# Detect220V.net
KiCad netlist of a schematic drawn in Altium Designer
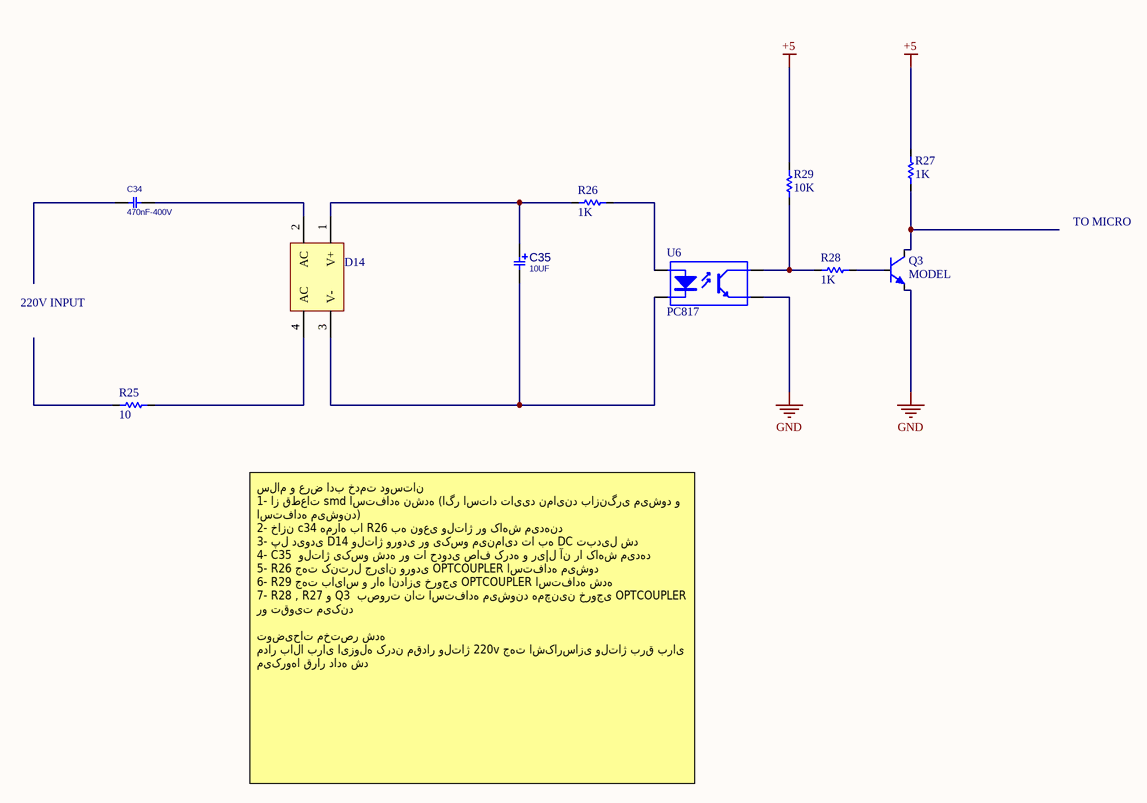
[diagram p0: Detect220V.SchDoc]

(export (version "E")
  (design (tool "Eeschema 10.0.6"))
  (components
    (comp (ref "C34")
      (value "470nF-400V")
      (footprint "C_PLY_6X2_5")
      (description "CAP, FILM,")
      (fields (field (name "MANF_P#") "MANF_PART#") (field (name "MANF") "MANF"))
      (libsource (lib "PASSIVE") (part "CAP_THD_FILM_POLYESTER"))
    )
    (comp (ref "C35")
      (value "10UF")
      (footprint "C_EL_4X7")
      (description "CAP, THD, ELEC,")
      (fields (field (name "MANF_P#") "MANF_PART#") (field (name "MANF") "MANF"))
      (libsource (lib "PASSIVE") (part "CAP_THD_EL"))
    )
    (comp (ref "D14")
      (value "DF04S")
      (footprint "DF005S")
      (description "Diode BRIDGE RECTIFIER DF04S 1A")
      (fields
        (field (name "MANUFACTURER") "VISHAY")
        (field (name "MANUFACTURER_1") "FAIRCHILD SEMICONDUCTOR")
        (field (name "DESIGNER") "Abbas Basereh")
      )
      (libsource (lib "2017AbbasBasereh9365731239 -ver1") (part "DF04S"))
    )
    (comp (ref "Q3")
      (value "MODEL")
      (footprint "TO-92")
      (description "NPN Bipolar Transistor")
      (libsource (lib "altium mahdi") (part "S8050"))
    )
    (comp (ref "R25")
      (value "10")
      (footprint "Res-(1/4)")
      (description "Resistor")
      (fields (field (name "TOLERANCE") "5%") (field (name "POWER") "1/4 W"))
      (libsource (lib "altium mahdi") (part "Resistor"))
    )
    (comp (ref "R26")
      (value "1K")
      (footprint "Res-(1/4)")
      (description "Resistor")
      (fields (field (name "TOLERANCE") "5%") (field (name "POWER") "1/4 W"))
      (libsource (lib "altium mahdi") (part "Resistor"))
    )
    (comp (ref "R27")
      (value "1K")
      (footprint "Res-(1/4)")
      (description "Resistor")
      (fields (field (name "TOLERANCE") "5%") (field (name "POWER") "1/4 W"))
      (libsource (lib "altium mahdi") (part "Resistor"))
    )
    (comp (ref "R28")
      (value "1K")
      (footprint "Res-(1/4)")
      (description "Resistor")
      (fields (field (name "TOLERANCE") "5%") (field (name "POWER") "1/4 W"))
      (libsource (lib "altium mahdi") (part "Resistor"))
    )
    (comp (ref "R29")
      (value "10K")
      (footprint "Res-(1/4)")
      (description "Resistor")
      (fields (field (name "TOLERANCE") "5%") (field (name "POWER") "1/4 W"))
      (libsource (lib "altium mahdi") (part "Resistor"))
    )
    (comp (ref "U6")
      (value "PC817")
      (footprint "DIP4")
      (description "4-Pin Phototransistor Optocoupler")
      (libsource (lib "altium mahdi") (part "OPTCOUPLER_01"))
    )
  )
  (nets
    (net (code "1") (name "+5") (class "Default")
      (node (ref "R27") (pin "2") (pinfunction "2_2") (pintype "passive"))
      (node (ref "R29") (pin "2") (pinfunction "2_2") (pintype "passive"))
    )
    (net (code "2") (name "GND") (class "Default")
      (node (ref "Q3") (pin "1") (pinfunction "E_1") (pintype "passive"))
      (node (ref "U6") (pin "3") (pinfunction "E_3") (pintype "passive"))
    )
    (net (code "3") (name "Net-(C34-Pad2)") (class "Default")
      (node (ref "C34") (pin "2") (pinfunction "2_2") (pintype "passive"))
      (node (ref "D14") (pin "2") (pinfunction "AC_2") (pintype "passive"))
    )
    (net (code "4") (name "Net-(D14-AC-Pad4)") (class "Default")
      (node (ref "D14") (pin "4") (pinfunction "AC_4") (pintype "passive"))
      (node (ref "R25") (pin "2") (pinfunction "2_2") (pintype "passive"))
    )
    (net (code "5") (name "Net-(D14-V+)") (class "Default")
      (node (ref "C35") (pin "1") (pinfunction "1_1") (pintype "passive"))
      (node (ref "D14") (pin "1") (pinfunction "V+_1") (pintype "passive"))
      (node (ref "R26") (pin "1") (pinfunction "1_1") (pintype "passive"))
    )
    (net (code "6") (name "Net-(D14-V-)") (class "Default")
      (node (ref "C35") (pin "2") (pinfunction "2_2") (pintype "passive"))
      (node (ref "D14") (pin "3") (pinfunction "V-_3") (pintype "passive"))
      (node (ref "U6") (pin "2") (pinfunction "K_2") (pintype "passive"))
    )
    (net (code "7") (name "Net-(Q3-B)") (class "Default")
      (node (ref "Q3") (pin "2") (pinfunction "B_2") (pintype "passive"))
      (node (ref "R28") (pin "2") (pinfunction "2_2") (pintype "passive"))
    )
    (net (code "8") (name "Net-(Q3-C)") (class "Default")
      (node (ref "Q3") (pin "3") (pinfunction "C_3") (pintype "passive"))
      (node (ref "R27") (pin "1") (pinfunction "1_1") (pintype "passive"))
    )
    (net (code "9") (name "Net-(U6-A)") (class "Default")
      (node (ref "R26") (pin "2") (pinfunction "2_2") (pintype "passive"))
      (node (ref "U6") (pin "1") (pinfunction "A_1") (pintype "passive"))
    )
    (net (code "10") (name "Net-(U6-C)") (class "Default")
      (node (ref "R28") (pin "1") (pinfunction "1_1") (pintype "passive"))
      (node (ref "R29") (pin "1") (pinfunction "1_1") (pintype "passive"))
      (node (ref "U6") (pin "4") (pinfunction "C_4") (pintype "passive"))
    )
    (net (code "11") (name "unconnected-(C34-Pad1)") (class "Default")
      (node (ref "C34") (pin "1") (pinfunction "1_1") (pintype "passive"))
    )
    (net (code "12") (name "unconnected-(R25-Pad1)") (class "Default")
      (node (ref "R25") (pin "1") (pinfunction "1_1") (pintype "passive"))
    )
  )
)
